# HandHeld_Terminal_V2.net
KiCad netlist of a schematic drawn in Altium Designer
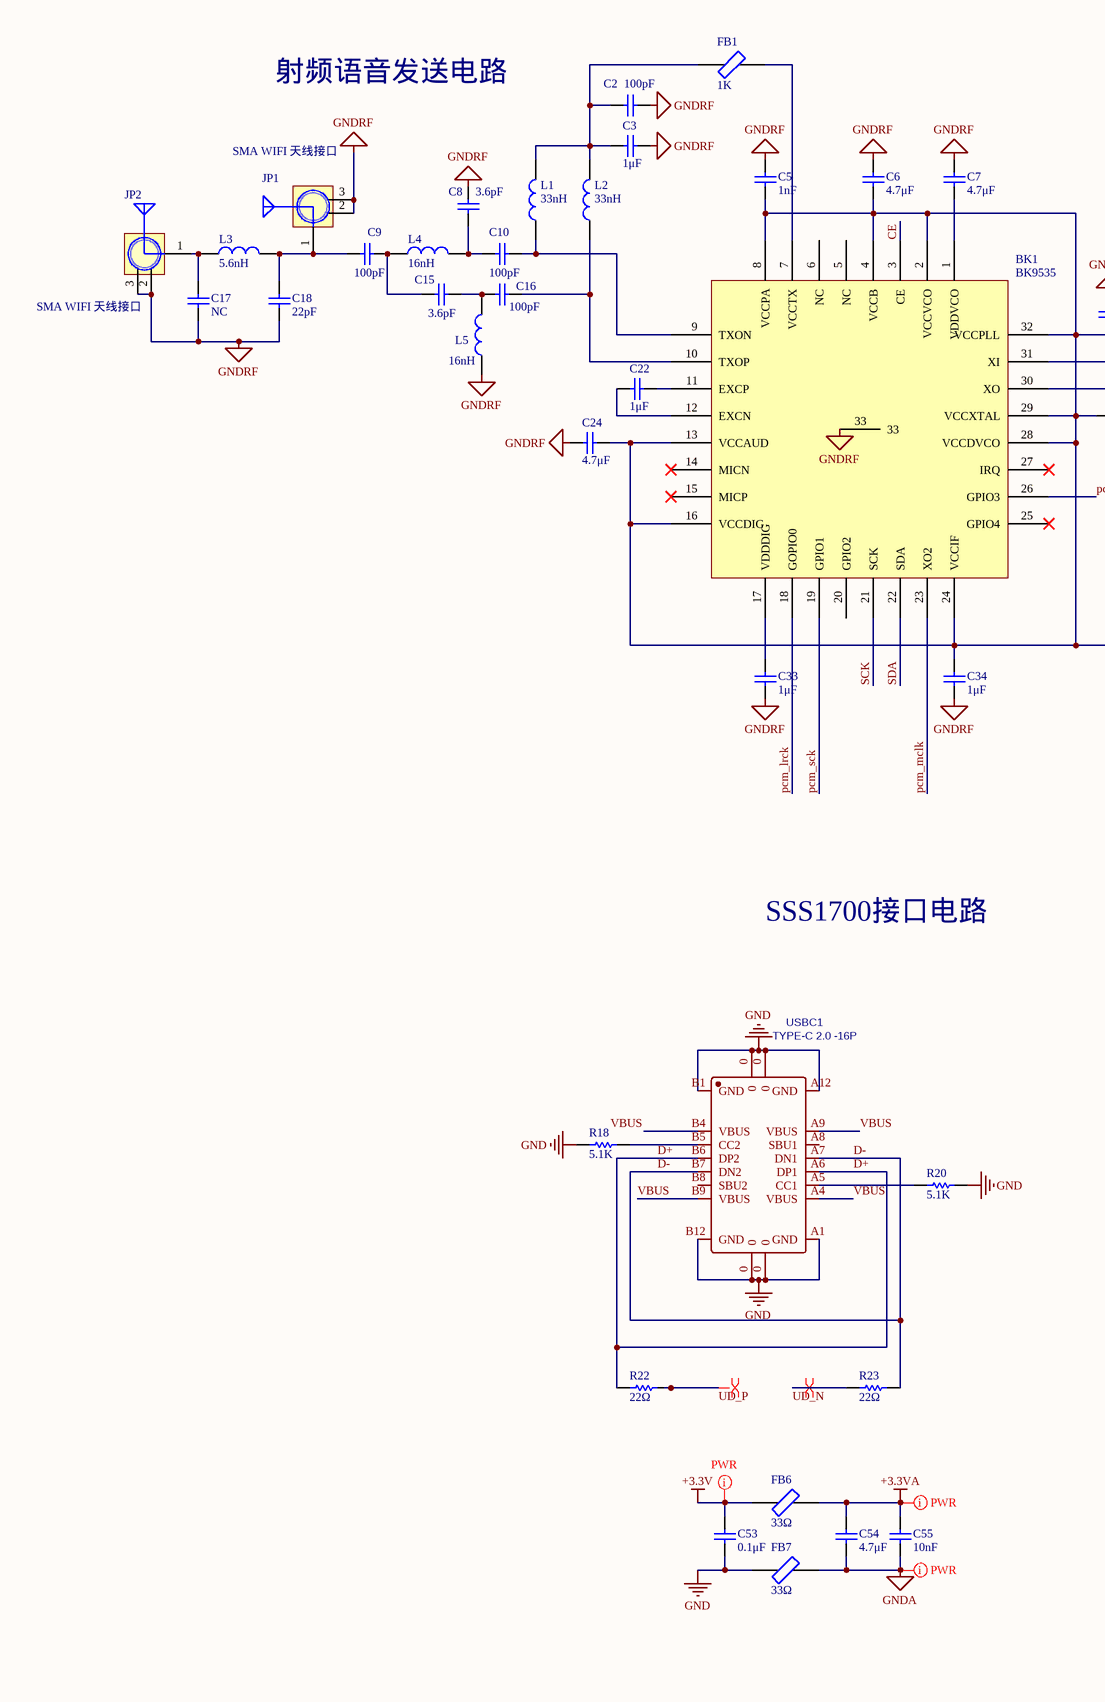
[diagram p0: HandHeld_Terminal_V2.SchDoc, left]
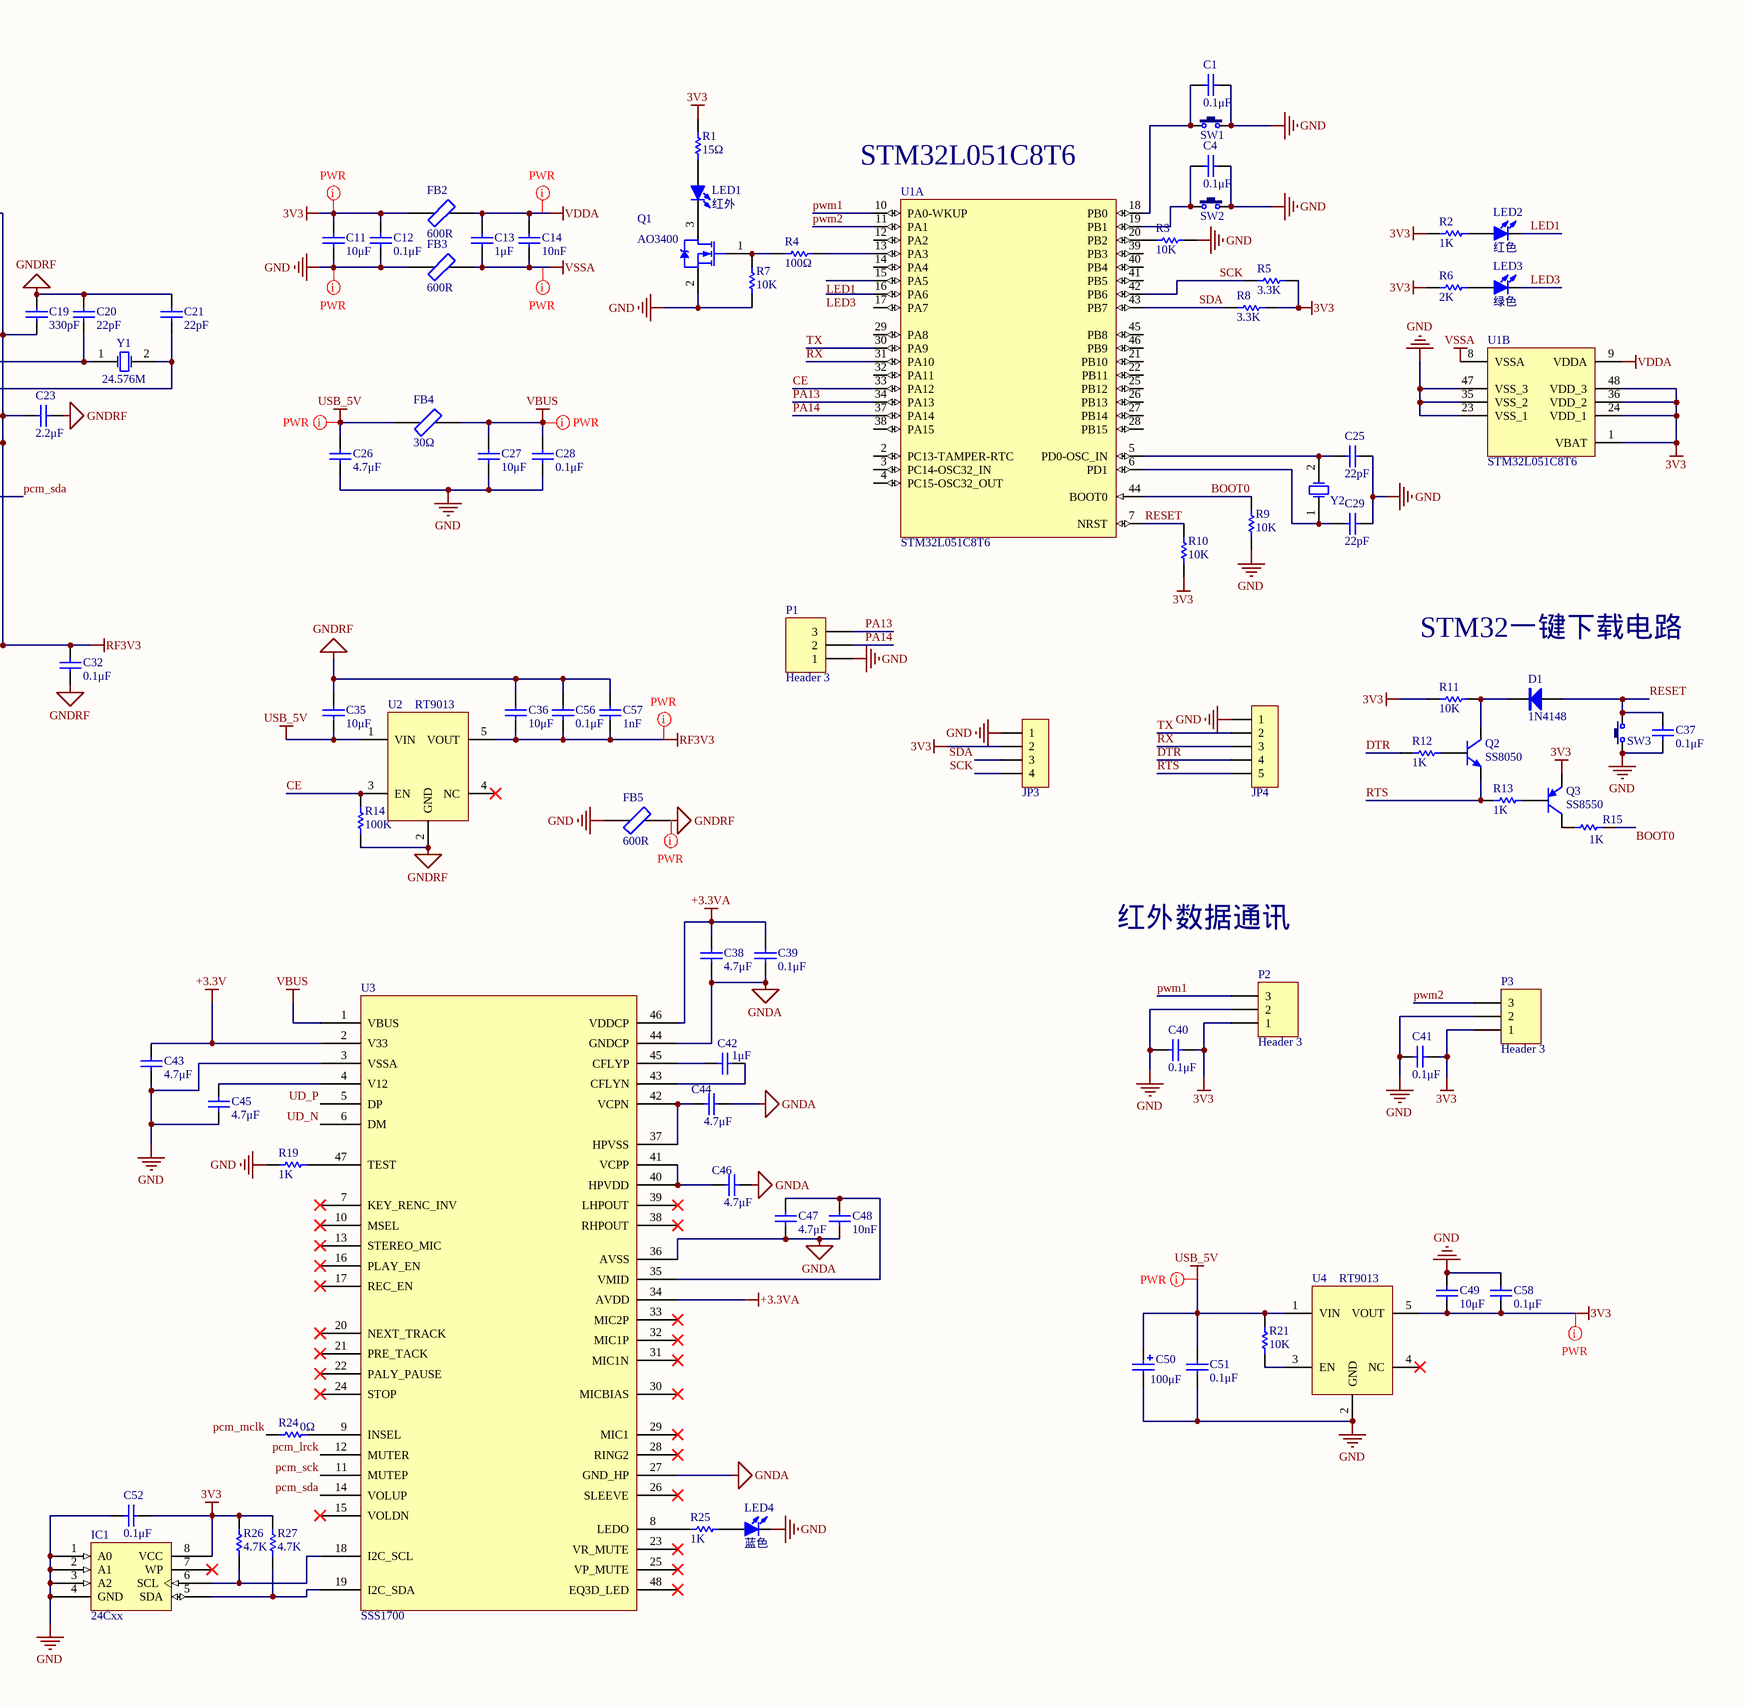
[diagram p1: HandHeld_Terminal_V2.SchDoc, right]

(export (version "E")
  (design (tool "Eeschema 10.0.6"))
  (components
    (comp (ref "BK1") (value "BK9535") (footprint "QFN32 5x5_N") (libsource (lib "Nixie") (part "BK9530")))
    (comp (ref "C1")
      (value "0.1μF")
      (footprint "C 0603_L")
      (description "Capacitor")
      (fields (field (name "Comment") "Cap") (field (name "PUBLISHER") "Altium Limited"))
      (libsource (lib "Nixie") (part "Cap"))
    )
    (comp (ref "C2")
      (value "100pF")
      (footprint "C 0603_L")
      (description "Capacitor")
      (fields (field (name "Comment") "Cap") (field (name "PUBLISHER") "Altium Limited"))
      (libsource (lib "Nixie") (part "Cap"))
    )
    (comp (ref "C3")
      (value "1μF")
      (footprint "C 0603_L")
      (description "Capacitor")
      (fields (field (name "Comment") "Cap") (field (name "PUBLISHER") "Altium Limited"))
      (libsource (lib "Nixie") (part "Cap"))
    )
    (comp (ref "C4")
      (value "0.1μF")
      (footprint "C 0603_L")
      (description "Capacitor")
      (fields (field (name "Comment") "Cap") (field (name "PUBLISHER") "Altium Limited"))
      (libsource (lib "Nixie") (part "Cap"))
    )
    (comp (ref "C5")
      (value "1nF")
      (footprint "C 0603_L")
      (description "Capacitor")
      (fields (field (name "Comment") "Cap") (field (name "PUBLISHER") "Altium Limited"))
      (libsource (lib "Nixie") (part "Cap"))
    )
    (comp (ref "C6")
      (value "4.7μF")
      (footprint "C 0603_L")
      (description "Capacitor")
      (fields (field (name "Comment") "Cap") (field (name "PUBLISHER") "Altium Limited"))
      (libsource (lib "Nixie") (part "Cap"))
    )
    (comp (ref "C7")
      (value "4.7μF")
      (footprint "C 0603_L")
      (description "Capacitor")
      (fields (field (name "Comment") "Cap") (field (name "PUBLISHER") "Altium Limited"))
      (libsource (lib "Nixie") (part "Cap"))
    )
    (comp (ref "C8")
      (value "3.6pF")
      (footprint "C 0603_L")
      (description "Capacitor")
      (fields (field (name "Comment") "Cap") (field (name "PUBLISHER") "Altium Limited"))
      (libsource (lib "Nixie") (part "Cap"))
    )
    (comp (ref "C9")
      (value "100pF")
      (footprint "C 0603_L")
      (description "Capacitor")
      (fields (field (name "Comment") "Cap") (field (name "PUBLISHER") "Altium Limited"))
      (libsource (lib "Nixie") (part "Cap"))
    )
    (comp (ref "C10")
      (value "100pF")
      (footprint "C 0603_L")
      (description "Capacitor")
      (fields (field (name "Comment") "Cap") (field (name "PUBLISHER") "Altium Limited"))
      (libsource (lib "Nixie") (part "Cap"))
    )
    (comp (ref "C11")
      (value "10μF")
      (footprint "C 0805_L")
      (description "Capacitor")
      (fields (field (name "Comment") "Cap") (field (name "PUBLISHER") "Altium Limited"))
      (libsource (lib "Nixie") (part "Cap"))
    )
    (comp (ref "C12")
      (value "0.1μF")
      (footprint "C 0603_L")
      (description "Capacitor")
      (fields (field (name "Comment") "Cap") (field (name "PUBLISHER") "Altium Limited"))
      (libsource (lib "Nixie") (part "Cap"))
    )
    (comp (ref "C13")
      (value "1μF")
      (footprint "C 0805_L")
      (description "Capacitor")
      (fields (field (name "Comment") "Cap") (field (name "PUBLISHER") "Altium Limited"))
      (libsource (lib "Nixie") (part "Cap"))
    )
    (comp (ref "C14")
      (value "10nF")
      (footprint "C 0805_L")
      (description "Capacitor")
      (fields (field (name "Comment") "Cap") (field (name "PUBLISHER") "Altium Limited"))
      (libsource (lib "Nixie") (part "Cap"))
    )
    (comp (ref "C15")
      (value "3.6pF")
      (footprint "C 0603_L")
      (description "Capacitor")
      (fields (field (name "Comment") "Cap") (field (name "PUBLISHER") "Altium Limited"))
      (libsource (lib "Nixie") (part "Cap"))
    )
    (comp (ref "C16")
      (value "100pF")
      (footprint "C 0603_L")
      (description "Capacitor")
      (fields (field (name "Comment") "Cap") (field (name "PUBLISHER") "Altium Limited"))
      (libsource (lib "Nixie") (part "Cap"))
    )
    (comp (ref "C17")
      (value "NC")
      (footprint "C 0603_L")
      (description "Capacitor")
      (fields (field (name "Comment") "Cap") (field (name "PUBLISHER") "Altium Limited"))
      (libsource (lib "Nixie") (part "Cap"))
    )
    (comp (ref "C18")
      (value "22pF")
      (footprint "C 0603_L")
      (description "Capacitor")
      (fields (field (name "Comment") "Cap") (field (name "PUBLISHER") "Altium Limited"))
      (libsource (lib "Nixie") (part "Cap"))
    )
    (comp (ref "C19")
      (value "330pF")
      (footprint "C 0603_L")
      (description "Capacitor")
      (fields (field (name "Comment") "Cap") (field (name "PUBLISHER") "Altium Limited"))
      (libsource (lib "Nixie") (part "Cap"))
    )
    (comp (ref "C20")
      (value "22pF")
      (footprint "C 0603_L")
      (description "Capacitor")
      (fields (field (name "Comment") "Cap") (field (name "PUBLISHER") "Altium Limited"))
      (libsource (lib "Nixie") (part "Cap"))
    )
    (comp (ref "C21")
      (value "22pF")
      (footprint "C 0603_L")
      (description "Capacitor")
      (fields (field (name "Comment") "Cap") (field (name "PUBLISHER") "Altium Limited"))
      (libsource (lib "Nixie") (part "Cap"))
    )
    (comp (ref "C22")
      (value "1μF")
      (footprint "C 0603_L")
      (description "Capacitor")
      (fields (field (name "Comment") "Cap") (field (name "PUBLISHER") "Altium Limited"))
      (libsource (lib "Nixie") (part "Cap"))
    )
    (comp (ref "C23")
      (value "2.2μF")
      (footprint "C 0603_L")
      (description "Capacitor")
      (fields (field (name "Comment") "Cap") (field (name "PUBLISHER") "Altium Limited"))
      (libsource (lib "Nixie") (part "Cap"))
    )
    (comp (ref "C24")
      (value "4.7μF")
      (footprint "C 0603_L")
      (description "Capacitor")
      (fields (field (name "Comment") "Cap") (field (name "PUBLISHER") "Altium Limited"))
      (libsource (lib "Nixie") (part "Cap"))
    )
    (comp (ref "C25")
      (value "22pF")
      (footprint "C 0603_L")
      (description "Capacitor")
      (fields (field (name "Comment") "Cap") (field (name "PUBLISHER") "Altium Limited"))
      (libsource (lib "Nixie") (part "Cap"))
    )
    (comp (ref "C26")
      (value "4.7μF")
      (footprint "C 0805_L")
      (description "Capacitor")
      (fields (field (name "Comment") "Cap") (field (name "PUBLISHER") "Altium Limited"))
      (libsource (lib "Nixie") (part "Cap"))
    )
    (comp (ref "C27")
      (value "10μF")
      (footprint "C 0805_L")
      (description "Capacitor")
      (fields (field (name "Comment") "Cap") (field (name "PUBLISHER") "Altium Limited"))
      (libsource (lib "Nixie") (part "Cap"))
    )
    (comp (ref "C28")
      (value "0.1μF")
      (footprint "C 0603_L")
      (description "Capacitor")
      (fields (field (name "Comment") "Cap") (field (name "PUBLISHER") "Altium Limited"))
      (libsource (lib "Nixie") (part "Cap"))
    )
    (comp (ref "C29")
      (value "22pF")
      (footprint "C 0603_L")
      (description "Capacitor")
      (fields (field (name "Comment") "Cap") (field (name "PUBLISHER") "Altium Limited"))
      (libsource (lib "Nixie") (part "Cap"))
    )
    (comp (ref "C32")
      (value "0.1μF")
      (footprint "C 0603_L")
      (description "Capacitor")
      (fields (field (name "Comment") "Cap") (field (name "PUBLISHER") "Altium Limited"))
      (libsource (lib "Nixie") (part "Cap"))
    )
    (comp (ref "C33")
      (value "1μF")
      (footprint "C 0603_L")
      (description "Capacitor")
      (fields (field (name "Comment") "Cap") (field (name "PUBLISHER") "Altium Limited"))
      (libsource (lib "Nixie") (part "Cap"))
    )
    (comp (ref "C34")
      (value "1μF")
      (footprint "C 0603_L")
      (description "Capacitor")
      (fields (field (name "Comment") "Cap") (field (name "PUBLISHER") "Altium Limited"))
      (libsource (lib "Nixie") (part "Cap"))
    )
    (comp (ref "C35")
      (value "10μF")
      (footprint "C 0805_L")
      (description "Capacitor")
      (fields (field (name "Comment") "Cap") (field (name "PUBLISHER") "Altium Limited"))
      (libsource (lib "Nixie") (part "Cap"))
    )
    (comp (ref "C36")
      (value "10μF")
      (footprint "C 0805_L")
      (description "Capacitor")
      (fields (field (name "Comment") "Cap") (field (name "PUBLISHER") "Altium Limited"))
      (libsource (lib "Nixie") (part "Cap"))
    )
    (comp (ref "C37")
      (value "0.1μF")
      (footprint "C 0603_L")
      (description "Capacitor")
      (fields (field (name "Comment") "Cap") (field (name "PUBLISHER") "Altium Limited"))
      (libsource (lib "Nixie") (part "Cap"))
    )
    (comp (ref "C38")
      (value "4.7μF")
      (footprint "C 0603_L")
      (description "Capacitor")
      (fields (field (name "Comment") "Cap") (field (name "PUBLISHER") "Altium Limited"))
      (libsource (lib "Nixie") (part "Cap"))
    )
    (comp (ref "C39")
      (value "0.1μF")
      (footprint "C 0603_L")
      (description "Capacitor")
      (fields (field (name "Comment") "Cap") (field (name "PUBLISHER") "Altium Limited"))
      (libsource (lib "Nixie") (part "Cap"))
    )
    (comp (ref "C40")
      (value "0.1μF")
      (footprint "C 0603_L")
      (description "Capacitor")
      (fields (field (name "Comment") "Cap") (field (name "PUBLISHER") "Altium Limited"))
      (libsource (lib "Nixie") (part "Cap"))
    )
    (comp (ref "C41")
      (value "0.1μF")
      (footprint "C 0603_L")
      (description "Capacitor")
      (fields (field (name "Comment") "Cap") (field (name "PUBLISHER") "Altium Limited"))
      (libsource (lib "Nixie") (part "Cap"))
    )
    (comp (ref "C42")
      (value "1μF")
      (footprint "C 0603_L")
      (description "Capacitor")
      (fields (field (name "Comment") "Cap") (field (name "PUBLISHER") "Altium Limited"))
      (libsource (lib "Nixie") (part "Cap"))
    )
    (comp (ref "C43")
      (value "4.7μF")
      (footprint "C 0603_L")
      (description "Capacitor")
      (fields (field (name "Comment") "Cap") (field (name "PUBLISHER") "Altium Limited"))
      (libsource (lib "Nixie") (part "Cap"))
    )
    (comp (ref "C44")
      (value "4.7μF")
      (footprint "C 0603_L")
      (description "Capacitor")
      (fields (field (name "Comment") "Cap") (field (name "PUBLISHER") "Altium Limited"))
      (libsource (lib "Nixie") (part "Cap"))
    )
    (comp (ref "C45")
      (value "4.7μF")
      (footprint "C 0603_L")
      (description "Capacitor")
      (fields (field (name "Comment") "Cap") (field (name "PUBLISHER") "Altium Limited"))
      (libsource (lib "Nixie") (part "Cap"))
    )
    (comp (ref "C46")
      (value "4.7μF")
      (footprint "C 0603_L")
      (description "Capacitor")
      (fields (field (name "Comment") "Cap") (field (name "PUBLISHER") "Altium Limited"))
      (libsource (lib "Nixie") (part "Cap"))
    )
    (comp (ref "C47")
      (value "4.7μF")
      (footprint "C 0603_L")
      (description "Capacitor")
      (fields (field (name "Comment") "Cap") (field (name "PUBLISHER") "Altium Limited"))
      (libsource (lib "Nixie") (part "Cap"))
    )
    (comp (ref "C48")
      (value "10nF")
      (footprint "C 0603_L")
      (description "Capacitor")
      (fields (field (name "Comment") "Cap") (field (name "PUBLISHER") "Altium Limited"))
      (libsource (lib "Nixie") (part "Cap"))
    )
    (comp (ref "C49")
      (value "10μF")
      (footprint "C 0805_L")
      (description "Capacitor")
      (fields (field (name "Comment") "Cap") (field (name "PUBLISHER") "Altium Limited"))
      (libsource (lib "Nixie") (part "Cap"))
    )
    (comp (ref "C50")
      (value "100μF")
      (footprint "CM C(5*5.4)")
      (description "Polarized Capacitor (Radial)")
      (fields (field (name "Comment") "Cap Pol1") (field (name "PUBLISHER") "Altium Limited"))
      (libsource (lib "Nixie") (part "Cap Pol1"))
    )
    (comp (ref "C51")
      (value "0.1μF")
      (footprint "C 0603_L")
      (description "Capacitor")
      (fields (field (name "Comment") "Cap") (field (name "PUBLISHER") "Altium Limited"))
      (libsource (lib "Nixie") (part "Cap"))
    )
    (comp (ref "C52")
      (value "0.1μF")
      (footprint "C 0603_L")
      (description "Capacitor")
      (fields (field (name "Comment") "Cap") (field (name "PUBLISHER") "Altium Limited"))
      (libsource (lib "Nixie") (part "Cap"))
    )
    (comp (ref "C53")
      (value "0.1μF")
      (footprint "C 0603_L")
      (description "Capacitor")
      (fields (field (name "Comment") "Cap") (field (name "PUBLISHER") "Altium Limited"))
      (libsource (lib "Nixie") (part "Cap"))
    )
    (comp (ref "C54")
      (value "4.7μF")
      (footprint "C 0805_L")
      (description "Capacitor")
      (fields (field (name "Comment") "Cap") (field (name "PUBLISHER") "Altium Limited"))
      (libsource (lib "Nixie") (part "Cap"))
    )
    (comp (ref "C55")
      (value "10nF")
      (footprint "C 0603_L")
      (description "Capacitor")
      (fields (field (name "Comment") "Cap") (field (name "PUBLISHER") "Altium Limited"))
      (libsource (lib "Nixie") (part "Cap"))
    )
    (comp (ref "C56")
      (value "0.1μF")
      (footprint "C 0603_L")
      (description "Capacitor")
      (fields (field (name "Comment") "Cap") (field (name "PUBLISHER") "Altium Limited"))
      (libsource (lib "Nixie") (part "Cap"))
    )
    (comp (ref "C57")
      (value "1nF")
      (footprint "C 0603_L")
      (description "Capacitor")
      (fields (field (name "Comment") "Cap") (field (name "PUBLISHER") "Altium Limited"))
      (libsource (lib "Nixie") (part "Cap"))
    )
    (comp (ref "C58")
      (value "0.1μF")
      (footprint "C 0603_L")
      (description "Capacitor")
      (fields (field (name "Comment") "Cap") (field (name "PUBLISHER") "Altium Limited"))
      (libsource (lib "Nixie") (part "Cap"))
    )
    (comp (ref "D1")
      (value "1N4148")
      (footprint "SOD-323")
      (description "开关二极管")
      (libsource (lib "Nixie") (part "1N4148"))
    )
    (comp (ref "FB1")
      (value "1K")
      (footprint "C 0603_L")
      (description "铁氧体磁珠")
      (fields (field (name "Comment") "Ferrite bead"))
      (libsource (lib "Nixie") (part "Ferrite bead"))
    )
    (comp (ref "FB2")
      (value "600R")
      (footprint "C 0603_L")
      (description "铁氧体磁珠")
      (fields (field (name "Comment") "Ferrite bead"))
      (libsource (lib "Nixie") (part "Ferrite bead"))
    )
    (comp (ref "FB3")
      (value "600R")
      (footprint "C 0603_L")
      (description "铁氧体磁珠")
      (fields (field (name "Comment") "Ferrite bead"))
      (libsource (lib "Nixie") (part "Ferrite bead"))
    )
    (comp (ref "FB4")
      (value "30Ω")
      (footprint "C 0603_L")
      (description "铁氧体磁珠")
      (fields (field (name "Comment") "Ferrite bead"))
      (libsource (lib "Nixie") (part "Ferrite bead"))
    )
    (comp (ref "FB5")
      (value "600R")
      (footprint "C 0805_L")
      (description "铁氧体磁珠")
      (fields (field (name "Comment") "Ferrite bead"))
      (libsource (lib "Nixie") (part "Ferrite bead"))
    )
    (comp (ref "FB6")
      (value "33Ω")
      (footprint "C 0603_L")
      (description "铁氧体磁珠")
      (fields (field (name "Comment") "Ferrite bead"))
      (libsource (lib "Nixie") (part "Ferrite bead"))
    )
    (comp (ref "FB7")
      (value "33Ω")
      (footprint "C 0603_L")
      (description "铁氧体磁珠")
      (fields (field (name "Comment") "Ferrite bead"))
      (libsource (lib "Nixie") (part "Ferrite bead"))
    )
    (comp (ref "IC1")
      (value "24Cxx")
      (footprint "SOP8_L")
      (description "外置EEPROM")
      (fields (field (name "版权归属") "封装库来自淘宝 ID：黄晶宝石"))
      (libsource (lib "Nixie") (part "24Cxx"))
    )
    (comp (ref "JP1")
      (value "SMA WIFI 天线接口")
      (footprint "COAXIAL/SMD/CON/V/I-PEX/W08-5801")
      (description "SMA-2.4G射频天线接口")
      (fields (field (name "版权归属") "封装库来自淘宝 ID：黄晶宝石"))
      (libsource (lib "") (part "SMA_1"))
    )
    (comp (ref "JP2")
      (value "SMA WIFI 天线接口")
      (footprint "SMA-KE")
      (description "SMA-2.4G射频天线接口")
      (fields (field (name "版权归属") "封装库来自淘宝 ID：黄晶宝石"))
      (libsource (lib "Nixie") (part "SMA"))
    )
    (comp (ref "JP3")
      (value "HDR-1X4")
      (footprint "HDR2.54-LI-4P")
      (description "4P接插件")
      (fields (field (name "版权归属") "封装库来自淘宝 ID：黄晶宝石"))
      (libsource (lib "Nixie") (part "Header 4"))
    )
    (comp (ref "JP4")
      (value "HDR-1X5")
      (footprint "HDR2.0-LI-5P")
      (description "5P接插件")
      (fields (field (name "版权归属") "封装库来自淘宝 ID：黄晶宝石"))
      (libsource (lib "Nixie") (part "Header 5"))
    )
    (comp (ref "L1")
      (value "33nH")
      (footprint "L 0603")
      (description "小功率贴片电感")
      (fields (field (name "Comment") "L"))
      (libsource (lib "Nixie") (part "L"))
    )
    (comp (ref "L2")
      (value "33nH")
      (footprint "L 0603")
      (description "小功率贴片电感")
      (fields (field (name "Comment") "L"))
      (libsource (lib "Nixie") (part "L"))
    )
    (comp (ref "L3")
      (value "5.6nH")
      (footprint "L 0603")
      (description "小功率贴片电感")
      (fields (field (name "Comment") "L"))
      (libsource (lib "Nixie") (part "L"))
    )
    (comp (ref "L4")
      (value "16nH")
      (footprint "L 0603")
      (description "小功率贴片电感")
      (fields (field (name "Comment") "L"))
      (libsource (lib "Nixie") (part "L"))
    )
    (comp (ref "L5")
      (value "16nH")
      (footprint "L 0603")
      (description "小功率贴片电感")
      (fields (field (name "Comment") "L"))
      (libsource (lib "Nixie") (part "L"))
    )
    (comp (ref "LED1")
      (value "红外")
      (footprint "LED 3MM-R")
      (description "贴片LED")
      (fields (field (name "版权归属") "封装库来自淘宝 ID：黄晶宝石"))
      (libsource (lib "Nixie") (part "LED-SMD"))
    )
    (comp (ref "LED2")
      (value "红色")
      (footprint "LED 0805R")
      (description "贴片LED")
      (fields (field (name "版权归属") "封装库来自淘宝 ID：黄晶宝石"))
      (libsource (lib "Nixie") (part "LED-SMD"))
    )
    (comp (ref "LED3")
      (value "绿色")
      (footprint "LED 0805G")
      (description "贴片LED")
      (fields (field (name "版权归属") "封装库来自淘宝 ID：黄晶宝石"))
      (libsource (lib "Nixie") (part "LED-SMD"))
    )
    (comp (ref "LED4")
      (value "蓝色")
      (footprint "LED 0805B")
      (description "贴片LED")
      (fields (field (name "版权归属") "封装库来自淘宝 ID：黄晶宝石"))
      (libsource (lib "Nixie") (part "LED-SMD"))
    )
    (comp (ref "P1")
      (value "Header 3")
      (footprint "HDR2.54-LI-3P")
      (description "Header, 3-Pin")
      (fields (field (name "PUBLISHER") "Altium Limited"))
      (libsource (lib "") (part "Header 3_1"))
    )
    (comp (ref "P2")
      (value "Header 3")
      (footprint "HDR1X3")
      (description "Header, 3-Pin")
      (fields (field (name "PUBLISHER") "Altium Limited"))
      (libsource (lib "Miscellaneous Connectors") (part "Header 3"))
    )
    (comp (ref "P3")
      (value "Header 3")
      (footprint "HDR1X3")
      (description "Header, 3-Pin")
      (fields (field (name "PUBLISHER") "Altium Limited"))
      (libsource (lib "Miscellaneous Connectors") (part "Header 3"))
    )
    (comp (ref "Q1")
      (value "AO3400")
      (footprint "SOT-23-3L")
      (description "N-Channel Power MOSFET")
      (fields (field (name "PUBLISHER") "Altium Limited"))
      (libsource (lib "Nixie") (part "NMOS-2"))
    )
    (comp (ref "Q2")
      (value "SS8050")
      (footprint "SOT-23-3L")
      (description "高频放大-NPN型")
      (fields (field (name "版权归属") "封装库来自淘宝 ID：黄晶宝石"))
      (libsource (lib "Nixie") (part "8050-SMD"))
    )
    (comp (ref "Q3")
      (value "SS8550")
      (footprint "SOT-23-3L")
      (description "高频放大-PNP型")
      (fields (field (name "版权归属") "封装库来自淘宝 ID：黄晶宝石"))
      (libsource (lib "Nixie") (part "8550-SMD"))
    )
    (comp (ref "R1")
      (value "15Ω")
      (footprint "R 1206_L")
      (description "Resistor")
      (fields (field (name "PUBLISHER") "Altium Limited"))
      (libsource (lib "Nixie") (part "Resistor"))
    )
    (comp (ref "R2")
      (value "1K")
      (footprint "R 0603_L")
      (description "Resistor")
      (fields (field (name "PUBLISHER") "Altium Limited"))
      (libsource (lib "Nixie") (part "Resistor"))
    )
    (comp (ref "R3")
      (value "10K")
      (footprint "R 0603_L")
      (description "Resistor")
      (fields (field (name "PUBLISHER") "Altium Limited"))
      (libsource (lib "Nixie") (part "Resistor"))
    )
    (comp (ref "R4")
      (value "100Ω")
      (footprint "R 0603_L")
      (description "Resistor")
      (fields (field (name "PUBLISHER") "Altium Limited"))
      (libsource (lib "Nixie") (part "Resistor"))
    )
    (comp (ref "R5")
      (value "3.3K")
      (footprint "R 0603_L")
      (description "Resistor")
      (fields (field (name "PUBLISHER") "Altium Limited"))
      (libsource (lib "Nixie") (part "Resistor"))
    )
    (comp (ref "R6")
      (value "2K")
      (footprint "R 0603_L")
      (description "Resistor")
      (fields (field (name "PUBLISHER") "Altium Limited"))
      (libsource (lib "Nixie") (part "Resistor"))
    )
    (comp (ref "R7")
      (value "10K")
      (footprint "R 0603_L")
      (description "Resistor")
      (fields (field (name "PUBLISHER") "Altium Limited"))
      (libsource (lib "Nixie") (part "Resistor"))
    )
    (comp (ref "R8")
      (value "3.3K")
      (footprint "R 0603_L")
      (description "Resistor")
      (fields (field (name "PUBLISHER") "Altium Limited"))
      (libsource (lib "Nixie") (part "Resistor"))
    )
    (comp (ref "R9")
      (value "10K")
      (footprint "R 0603_L")
      (description "Resistor")
      (fields (field (name "PUBLISHER") "Altium Limited"))
      (libsource (lib "Nixie") (part "Resistor"))
    )
    (comp (ref "R10")
      (value "10K")
      (footprint "R 0603_L")
      (description "Resistor")
      (fields (field (name "PUBLISHER") "Altium Limited"))
      (libsource (lib "Nixie") (part "Resistor"))
    )
    (comp (ref "R11")
      (value "10K")
      (footprint "R 0603_L")
      (description "Resistor")
      (fields (field (name "PUBLISHER") "Altium Limited"))
      (libsource (lib "Nixie") (part "Resistor"))
    )
    (comp (ref "R12")
      (value "1K")
      (footprint "R 0603_L")
      (description "Resistor")
      (fields (field (name "PUBLISHER") "Altium Limited"))
      (libsource (lib "Nixie") (part "Resistor"))
    )
    (comp (ref "R13")
      (value "1K")
      (footprint "R 0603_L")
      (description "Resistor")
      (fields (field (name "PUBLISHER") "Altium Limited"))
      (libsource (lib "Nixie") (part "Resistor"))
    )
    (comp (ref "R14")
      (value "100K")
      (footprint "R 0603_L")
      (description "Resistor")
      (fields (field (name "PUBLISHER") "Altium Limited"))
      (libsource (lib "Nixie") (part "Resistor"))
    )
    (comp (ref "R15")
      (value "1K")
      (footprint "R 0603_L")
      (description "Resistor")
      (fields (field (name "PUBLISHER") "Altium Limited"))
      (libsource (lib "Nixie") (part "Resistor"))
    )
    (comp (ref "R18")
      (value "5.1K")
      (footprint "R 0603_L")
      (description "Resistor")
      (fields (field (name "PUBLISHER") "Altium Limited"))
      (libsource (lib "Nixie") (part "Resistor"))
    )
    (comp (ref "R19")
      (value "1K")
      (footprint "R 0603_L")
      (description "Resistor")
      (fields (field (name "PUBLISHER") "Altium Limited"))
      (libsource (lib "Nixie") (part "Resistor"))
    )
    (comp (ref "R20")
      (value "5.1K")
      (footprint "R 0603_L")
      (description "Resistor")
      (fields (field (name "PUBLISHER") "Altium Limited"))
      (libsource (lib "Nixie") (part "Resistor"))
    )
    (comp (ref "R21")
      (value "10K")
      (footprint "R 0603_L")
      (description "Resistor")
      (fields (field (name "PUBLISHER") "Altium Limited"))
      (libsource (lib "Nixie") (part "Resistor"))
    )
    (comp (ref "R22")
      (value "22Ω")
      (footprint "R 0603_L")
      (description "Resistor")
      (fields (field (name "PUBLISHER") "Altium Limited"))
      (libsource (lib "Nixie") (part "Resistor"))
    )
    (comp (ref "R23")
      (value "22Ω")
      (footprint "R 0603_L")
      (description "Resistor")
      (fields (field (name "PUBLISHER") "Altium Limited"))
      (libsource (lib "Nixie") (part "Resistor"))
    )
    (comp (ref "R24")
      (value "0Ω")
      (footprint "R 0603_L")
      (description "Resistor")
      (fields (field (name "PUBLISHER") "Altium Limited"))
      (libsource (lib "Nixie") (part "Resistor"))
    )
    (comp (ref "R25")
      (value "1K")
      (footprint "R 0603_L")
      (description "Resistor")
      (fields (field (name "PUBLISHER") "Altium Limited"))
      (libsource (lib "Nixie") (part "Resistor"))
    )
    (comp (ref "R26")
      (value "4.7K")
      (footprint "R 0603_L")
      (description "Resistor")
      (fields (field (name "PUBLISHER") "Altium Limited"))
      (libsource (lib "Nixie") (part "Resistor"))
    )
    (comp (ref "R27")
      (value "4.7K")
      (footprint "R 0603_L")
      (description "Resistor")
      (fields (field (name "PUBLISHER") "Altium Limited"))
      (libsource (lib "Nixie") (part "Resistor"))
    )
    (comp (ref "SW1")
      (value "3x6x5")
      (footprint "TSW SMD-3*6*2.5")
      (description "3x6轻触开关")
      (fields (field (name "版权归属") "封装库来自淘宝 ID：黄晶宝石"))
      (libsource (lib "") (part "TSW 3x6_1"))
    )
    (comp (ref "SW2")
      (value "3x6x5")
      (footprint "TSW SMD-3*6*2.5")
      (description "3x6轻触开关")
      (fields (field (name "版权归属") "封装库来自淘宝 ID：黄晶宝石"))
      (libsource (lib "") (part "TSW 3x6_1"))
    )
    (comp (ref "SW3")
      (value "3x6x5")
      (footprint "TSW SMD-3*6*2.5")
      (description "3x6轻触开关")
      (fields (field (name "版权归属") "封装库来自淘宝 ID：黄晶宝石"))
      (libsource (lib "Nixie") (part "TSW 3x6"))
    )
    (comp (ref "U1")
      (value "STM32L051C8T6")
      (footprint "LQFP48_L")
      (description "ARM")
      (libsource (lib "Nixie") (part "STM32F103C8T6"))
    )
    (comp (ref "U2")
      (value "RT9013")
      (footprint "SOT23-5L")
      (description "LDO")
      (libsource (lib "HandHeld_terminal") (part "RT9013"))
    )
    (comp (ref "U3")
      (value "SSS1700")
      (footprint "LQFP48_L")
      (description "USB音频芯片")
      (libsource (lib "Nixie") (part "SSS1700"))
    )
    (comp (ref "U4")
      (value "RT9013")
      (footprint "SOT23-5L")
      (description "LDO")
      (libsource (lib "HandHeld_terminal") (part "RT9013"))
    )
    (comp (ref "USBC1")
      (value "TYPE-C 2.0 -16P")
      (footprint "USB-C-SMD_TYPE-C-USB-5")
      (description "USB2.0 Type-C 母座 16Pin")
      (libsource (lib "Nixie") (part "USB2.0 Type-C 16Pin母座"))
    )
    (comp (ref "Y1")
      (value "24.576M")
      (footprint "OSC 5032-2P")
      (description "Crystal Oscillator")
      (fields (field (name "PUBLISHER") "Altium Limited"))
      (libsource (lib "Miscellaneous Devices") (part "XTAL"))
    )
    (comp (ref "Y2")
      (value "8MHz ±20ppm 20pF")
      (footprint "OSC 5032-2P")
      (description "贴片晶振")
      (libsource (lib "HandHeld_terminal") (part "SMD-5032_2P 8MHz 20ppm 20pF"))
    )
  )
  (nets
    (net (code "1") (name "+3.3V") (class "Default")
      (node (ref "C43") (pin "2") (pinfunction "2_2") (pintype "passive"))
      (node (ref "C53") (pin "2") (pinfunction "2_2") (pintype "passive"))
      (node (ref "FB6") (pin "1") (pinfunction "1_1") (pintype "passive"))
      (node (ref "U3") (pin "2") (pinfunction "V33_2") (pintype "passive"))
    )
    (net (code "2") (name "+3.3VA") (class "Default")
      (node (ref "C38") (pin "2") (pinfunction "2_2") (pintype "passive"))
      (node (ref "C39") (pin "2") (pinfunction "2_2") (pintype "passive"))
      (node (ref "C54") (pin "2") (pinfunction "2_2") (pintype "passive"))
      (node (ref "C55") (pin "2") (pinfunction "2_2") (pintype "passive"))
      (node (ref "FB6") (pin "2") (pinfunction "2_2") (pintype "passive"))
      (node (ref "U3") (pin "34") (pinfunction "AVDD_34") (pintype "passive"))
      (node (ref "U3") (pin "46") (pinfunction "VDDCP_46") (pintype "passive"))
    )
    (net (code "3") (name "/BOOT0") (class "Default")
      (node (ref "R15") (pin "2") (pinfunction "2_2") (pintype "passive"))
      (node (ref "R9") (pin "1") (pinfunction "1_1") (pintype "passive"))
      (node (ref "U1") (pin "44") (pinfunction "BOOT0_44") (pintype "input"))
    )
    (net (code "4") (name "/CE") (class "Default")
      (node (ref "BK1") (pin "3") (pinfunction "CE_3") (pintype "passive"))
      (node (ref "R14") (pin "2") (pinfunction "2_2") (pintype "passive"))
      (node (ref "U1") (pin "33") (pinfunction "PA12_33") (pintype "bidirectional"))
      (node (ref "U2") (pin "3") (pinfunction "EN_3") (pintype "passive"))
    )
    (net (code "5") (name "/D+") (class "Default")
      (node (ref "R22") (pin "1") (pinfunction "1_1") (pintype "passive"))
      (node (ref "USBC1") (pin "A6") (pinfunction "DP1_A6") (pintype "passive"))
      (node (ref "USBC1") (pin "B6") (pinfunction "DP2_B6") (pintype "passive"))
    )
    (net (code "6") (name "/D-") (class "Default")
      (node (ref "R23") (pin "2") (pinfunction "2_2") (pintype "passive"))
      (node (ref "USBC1") (pin "A7") (pinfunction "DN1_A7") (pintype "passive"))
      (node (ref "USBC1") (pin "B7") (pinfunction "DN2_B7") (pintype "passive"))
    )
    (net (code "7") (name "/DTR") (class "Default")
      (node (ref "JP4") (pin "4") (pinfunction "4_4") (pintype "passive"))
      (node (ref "R12") (pin "1") (pinfunction "1_1") (pintype "passive"))
    )
    (net (code "8") (name "/LED1") (class "Default")
      (node (ref "LED2") (pin "2") (pinfunction "K_2") (pintype "passive"))
      (node (ref "U1") (pin "15") (pinfunction "PA5_15") (pintype "bidirectional"))
    )
    (net (code "9") (name "/LED3") (class "Default")
      (node (ref "LED3") (pin "2") (pinfunction "K_2") (pintype "passive"))
      (node (ref "U1") (pin "16") (pinfunction "PA6_16") (pintype "bidirectional"))
    )
    (net (code "10") (name "/PA13") (class "Default")
      (node (ref "P1") (pin "3") (pinfunction "3_3") (pintype "passive"))
      (node (ref "U1") (pin "34") (pinfunction "PA13_34") (pintype "bidirectional"))
    )
    (net (code "11") (name "/PA14") (class "Default")
      (node (ref "P1") (pin "2") (pinfunction "2_2") (pintype "passive"))
      (node (ref "U1") (pin "37") (pinfunction "PA14_37") (pintype "bidirectional"))
    )
    (net (code "12") (name "/RESET") (class "Default")
      (node (ref "C37") (pin "2") (pinfunction "2_2") (pintype "passive"))
      (node (ref "D1") (pin "1") (pinfunction "A_1") (pintype "passive"))
      (node (ref "R10") (pin "1") (pinfunction "1_1") (pintype "passive"))
      (node (ref "SW3") (pin "2") (pinfunction "2_2") (pintype "passive"))
      (node (ref "U1") (pin "7") (pinfunction "NRST_7") (pintype "bidirectional"))
    )
    (net (code "13") (name "/RTS") (class "Default")
      (node (ref "JP4") (pin "5") (pinfunction "5_5") (pintype "passive"))
      (node (ref "Q2") (pin "2") (pinfunction "E_2") (pintype "passive"))
      (node (ref "R13") (pin "1") (pinfunction "1_1") (pintype "passive"))
    )
    (net (code "14") (name "/RX") (class "Default")
      (node (ref "JP4") (pin "3") (pinfunction "3_3") (pintype "passive"))
      (node (ref "U1") (pin "31") (pinfunction "PA10_31") (pintype "bidirectional"))
    )
    (net (code "15") (name "/SCK") (class "Default")
      (node (ref "BK1") (pin "21") (pinfunction "SCK_21") (pintype "passive"))
      (node (ref "JP3") (pin "4") (pinfunction "4_4") (pintype "passive"))
      (node (ref "R5") (pin "2") (pinfunction "2_2") (pintype "passive"))
      (node (ref "U1") (pin "42") (pinfunction "PB6_42") (pintype "bidirectional"))
    )
    (net (code "16") (name "/SDA") (class "Default")
      (node (ref "BK1") (pin "22") (pinfunction "SDA_22") (pintype "passive"))
      (node (ref "JP3") (pin "3") (pinfunction "3_3") (pintype "passive"))
      (node (ref "R8") (pin "2") (pinfunction "2_2") (pintype "passive"))
      (node (ref "U1") (pin "43") (pinfunction "PB7_43") (pintype "bidirectional"))
    )
    (net (code "17") (name "/TX") (class "Default")
      (node (ref "JP4") (pin "2") (pinfunction "2_2") (pintype "passive"))
      (node (ref "U1") (pin "30") (pinfunction "PA9_30") (pintype "bidirectional"))
    )
    (net (code "18") (name "/UD_N") (class "Default")
      (node (ref "R23") (pin "1") (pinfunction "1_1") (pintype "passive"))
      (node (ref "U3") (pin "6") (pinfunction "DM_6") (pintype "passive"))
    )
    (net (code "19") (name "/UD_P") (class "Default")
      (node (ref "R22") (pin "2") (pinfunction "2_2") (pintype "passive"))
      (node (ref "U3") (pin "5") (pinfunction "DP_5") (pintype "passive"))
    )
    (net (code "20") (name "/pcm_lrck") (class "Default")
      (node (ref "BK1") (pin "18") (pinfunction "GOPIO0_18") (pintype "passive"))
      (node (ref "U3") (pin "12") (pinfunction "MUTER_12") (pintype "passive"))
    )
    (net (code "21") (name "/pcm_mclk") (class "Default")
      (node (ref "BK1") (pin "23") (pinfunction "XO2_23") (pintype "passive"))
      (node (ref "R24") (pin "2") (pinfunction "2_2") (pintype "passive"))
    )
    (net (code "22") (name "/pcm_sck") (class "Default")
      (node (ref "BK1") (pin "19") (pinfunction "GPIO1_19") (pintype "passive"))
      (node (ref "U3") (pin "11") (pinfunction "MUTEP_11") (pintype "passive"))
    )
    (net (code "23") (name "/pcm_sda") (class "Default")
      (node (ref "BK1") (pin "26") (pinfunction "GPIO3_26") (pintype "passive"))
      (node (ref "U3") (pin "14") (pinfunction "VOLUP_14") (pintype "passive"))
    )
    (net (code "24") (name "/pwm1") (class "Default")
      (node (ref "P2") (pin "3") (pinfunction "3_3") (pintype "passive"))
      (node (ref "U1") (pin "10") (pinfunction "PA0-WKUP_10") (pintype "bidirectional"))
    )
    (net (code "25") (name "/pwm2") (class "Default")
      (node (ref "P3") (pin "3") (pinfunction "3_3") (pintype "passive"))
      (node (ref "U1") (pin "11") (pinfunction "PA1_11") (pintype "bidirectional"))
    )
    (net (code "26") (name "3V3") (class "Default")
      (node (ref "C11") (pin "2") (pinfunction "2_2") (pintype "passive"))
      (node (ref "C12") (pin "2") (pinfunction "2_2") (pintype "passive"))
      (node (ref "C40") (pin "1") (pinfunction "1_1") (pintype "passive"))
      (node (ref "C41") (pin "1") (pinfunction "1_1") (pintype "passive"))
      (node (ref "C49") (pin "1") (pinfunction "1_1") (pintype "passive"))
      (node (ref "C52") (pin "1") (pinfunction "1_1") (pintype "passive"))
      (node (ref "C58") (pin "2") (pinfunction "2_2") (pintype "passive"))
      (node (ref "FB2") (pin "1") (pinfunction "1_1") (pintype "passive"))
      (node (ref "IC1") (pin "8") (pinfunction "VCC_8") (pintype "power_in"))
      (node (ref "JP3") (pin "2") (pinfunction "2_2") (pintype "passive"))
      (node (ref "P2") (pin "1") (pinfunction "1_1") (pintype "passive"))
      (node (ref "P3") (pin "1") (pinfunction "1_1") (pintype "passive"))
      (node (ref "Q3") (pin "2") (pinfunction "E_2") (pintype "passive"))
      (node (ref "R1") (pin "2") (pinfunction "2_2") (pintype "passive"))
      (node (ref "R10") (pin "2") (pinfunction "2_2") (pintype "passive"))
      (node (ref "R11") (pin "1") (pinfunction "1_1") (pintype "passive"))
      (node (ref "R2") (pin "2") (pinfunction "2_2") (pintype "passive"))
      (node (ref "R26") (pin "2") (pinfunction "2_2") (pintype "passive"))
      (node (ref "R27") (pin "2") (pinfunction "2_2") (pintype "passive"))
      (node (ref "R5") (pin "1") (pinfunction "1_1") (pintype "passive"))
      (node (ref "R6") (pin "2") (pinfunction "2_2") (pintype "passive"))
      (node (ref "R8") (pin "1") (pinfunction "1_1") (pintype "passive"))
      (node (ref "U1") (pin "1") (pinfunction "VBAT_1") (pintype "power_in"))
      (node (ref "U1") (pin "24") (pinfunction "VDD_1_24") (pintype "power_in"))
      (node (ref "U1") (pin "36") (pinfunction "VDD_2_36") (pintype "power_in"))
      (node (ref "U1") (pin "48") (pinfunction "VDD_3_48") (pintype "power_in"))
      (node (ref "U4") (pin "5") (pinfunction "VOUT_5") (pintype "passive"))
    )
    (net (code "27") (name "GND") (class "Default")
      (node (ref "C1") (pin "1") (pinfunction "1_1") (pintype "passive"))
      (node (ref "C11") (pin "1") (pinfunction "1_1") (pintype "passive"))
      (node (ref "C12") (pin "1") (pinfunction "1_1") (pintype "passive"))
      (node (ref "C25") (pin "1") (pinfunction "1_1") (pintype "passive"))
      (node (ref "C26") (pin "1") (pinfunction "1_1") (pintype "passive"))
      (node (ref "C27") (pin "1") (pinfunction "1_1") (pintype "passive"))
      (node (ref "C28") (pin "1") (pinfunction "1_1") (pintype "passive"))
      (node (ref "C29") (pin "1") (pinfunction "1_1") (pintype "passive"))
      (node (ref "C37") (pin "1") (pinfunction "1_1") (pintype "passive"))
      (node (ref "C4") (pin "1") (pinfunction "1_1") (pintype "passive"))
      (node (ref "C40") (pin "2") (pinfunction "2_2") (pintype "passive"))
      (node (ref "C41") (pin "2") (pinfunction "2_2") (pintype "passive"))
      (node (ref "C43") (pin "1") (pinfunction "1_1") (pintype "passive"))
      (node (ref "C45") (pin "1") (pinfunction "1_1") (pintype "passive"))
      (node (ref "C49") (pin "2") (pinfunction "2_2") (pintype "passive"))
      (node (ref "C50") (pin "2") (pinfunction "2_2") (pintype "passive"))
      (node (ref "C51") (pin "2") (pinfunction "2_2") (pintype "passive"))
      (node (ref "C52") (pin "2") (pinfunction "2_2") (pintype "passive"))
      (node (ref "C53") (pin "1") (pinfunction "1_1") (pintype "passive"))
      (node (ref "C58") (pin "1") (pinfunction "1_1") (pintype "passive"))
      (node (ref "FB3") (pin "1") (pinfunction "1_1") (pintype "passive"))
      (node (ref "FB5") (pin "1") (pinfunction "1_1") (pintype "passive"))
      (node (ref "FB7") (pin "1") (pinfunction "1_1") (pintype "passive"))
      (node (ref "IC1") (pin "1") (pinfunction "A0_1") (pintype "input"))
      (node (ref "IC1") (pin "2") (pinfunction "A1_2") (pintype "input"))
      (node (ref "IC1") (pin "3") (pinfunction "A2_3") (pintype "input"))
      (node (ref "IC1") (pin "4") (pinfunction "GND_4") (pintype "passive"))
      (node (ref "JP3") (pin "1") (pinfunction "1_1") (pintype "passive"))
      (node (ref "JP4") (pin "1") (pinfunction "1_1") (pintype "passive"))
      (node (ref "LED4") (pin "2") (pinfunction "K_2") (pintype "passive"))
      (node (ref "P1") (pin "1") (pinfunction "1_1") (pintype "passive"))
      (node (ref "P2") (pin "2") (pinfunction "2_2") (pintype "passive"))
      (node (ref "P3") (pin "2") (pinfunction "2_2") (pintype "passive"))
      (node (ref "Q1") (pin "2") (pinfunction "S_2") (pintype "passive"))
      (node (ref "R18") (pin "2") (pinfunction "2_2") (pintype "passive"))
      (node (ref "R19") (pin "2") (pinfunction "2_2") (pintype "passive"))
      (node (ref "R20") (pin "1") (pinfunction "1_1") (pintype "passive"))
      (node (ref "R3") (pin "2") (pinfunction "2_2") (pintype "passive"))
      (node (ref "R7") (pin "1") (pinfunction "1_1") (pintype "passive"))
      (node (ref "R9") (pin "2") (pinfunction "2_2") (pintype "passive"))
      (node (ref "SW1") (pin "2") (pinfunction "2_2") (pintype "passive"))
      (node (ref "SW2") (pin "2") (pinfunction "2_2") (pintype "passive"))
      (node (ref "SW3") (pin "1") (pinfunction "1_1") (pintype "passive"))
      (node (ref "U1") (pin "23") (pinfunction "VSS_1_23") (pintype "power_in"))
      (node (ref "U1") (pin "35") (pinfunction "VSS_2_35") (pintype "power_in"))
      (node (ref "U1") (pin "47") (pinfunction "VSS_3_47") (pintype "power_in"))
      (node (ref "U3") (pin "3") (pinfunction "VSSA_3") (pintype "passive"))
      (node (ref "U4") (pin "2") (pinfunction "GND_2") (pintype "passive"))
      (node (ref "USBC1") (pin "0") (pinfunction "0_0") (pintype "passive"))
      (node (ref "USBC1") (pin "A1") (pinfunction "GND_A1") (pintype "passive"))
      (node (ref "USBC1") (pin "A12") (pinfunction "GND_A12") (pintype "passive"))
      (node (ref "USBC1") (pin "B1") (pinfunction "GND_B1") (pintype "passive"))
      (node (ref "USBC1") (pin "B12") (pinfunction "GND_B12") (pintype "passive"))
    )
    (net (code "28") (name "GNDA") (class "Default")
      (node (ref "C38") (pin "1") (pinfunction "1_1") (pintype "passive"))
      (node (ref "C39") (pin "1") (pinfunction "1_1") (pintype "passive"))
      (node (ref "C44") (pin "1") (pinfunction "1_1") (pintype "passive"))
      (node (ref "C46") (pin "1") (pinfunction "1_1") (pintype "passive"))
      (node (ref "C47") (pin "1") (pinfunction "1_1") (pintype "passive"))
      (node (ref "C48") (pin "1") (pinfunction "1_1") (pintype "passive"))
      (node (ref "C54") (pin "1") (pinfunction "1_1") (pintype "passive"))
      (node (ref "C55") (pin "1") (pinfunction "1_1") (pintype "passive"))
      (node (ref "FB7") (pin "2") (pinfunction "2_2") (pintype "passive"))
      (node (ref "U3") (pin "27") (pinfunction "GND_HP_27") (pintype "passive"))
      (node (ref "U3") (pin "36") (pinfunction "AVSS_36") (pintype "passive"))
      (node (ref "U3") (pin "44") (pinfunction "GNDCP_44") (pintype "passive"))
    )
    (net (code "29") (name "GNDRF") (class "Default")
      (node (ref "BK1") (pin "33") (pinfunction "33_33") (pintype "passive"))
      (node (ref "C17") (pin "2") (pinfunction "2_2") (pintype "passive"))
      (node (ref "C18") (pin "2") (pinfunction "2_2") (pintype "passive"))
      (node (ref "C19") (pin "2") (pinfunction "2_2") (pintype "passive"))
      (node (ref "C2") (pin "1") (pinfunction "1_1") (pintype "passive"))
      (node (ref "C20") (pin "2") (pinfunction "2_2") (pintype "passive"))
      (node (ref "C21") (pin "2") (pinfunction "2_2") (pintype "passive"))
      (node (ref "C23") (pin "1") (pinfunction "1_1") (pintype "passive"))
      (node (ref "C24") (pin "2") (pinfunction "2_2") (pintype "passive"))
      (node (ref "C3") (pin "1") (pinfunction "1_1") (pintype "passive"))
      (node (ref "C32") (pin "1") (pinfunction "1_1") (pintype "passive"))
      (node (ref "C33") (pin "1") (pinfunction "1_1") (pintype "passive"))
      (node (ref "C34") (pin "1") (pinfunction "1_1") (pintype "passive"))
      (node (ref "C35") (pin "2") (pinfunction "2_2") (pintype "passive"))
      (node (ref "C36") (pin "2") (pinfunction "2_2") (pintype "passive"))
      (node (ref "C5") (pin "1") (pinfunction "1_1") (pintype "passive"))
      (node (ref "C56") (pin "2") (pinfunction "2_2") (pintype "passive"))
      (node (ref "C57") (pin "1") (pinfunction "1_1") (pintype "passive"))
      (node (ref "C6") (pin "1") (pinfunction "1_1") (pintype "passive"))
      (node (ref "C7") (pin "1") (pinfunction "1_1") (pintype "passive"))
      (node (ref "C8") (pin "1") (pinfunction "1_1") (pintype "passive"))
      (node (ref "FB5") (pin "2") (pinfunction "2_2") (pintype "passive"))
      (node (ref "JP1") (pin "2") (pinfunction "GND_2") (pintype "passive"))
      (node (ref "JP1") (pin "3") (pinfunction "GND_3") (pintype "passive"))
      (node (ref "JP2") (pin "2") (pinfunction "GND_2") (pintype "passive"))
      (node (ref "JP2") (pin "3") (pinfunction "GND_3") (pintype "passive"))
      (node (ref "L5") (pin "1") (pinfunction "1_1") (pintype "passive"))
      (node (ref "R14") (pin "1") (pinfunction "1_1") (pintype "passive"))
      (node (ref "U2") (pin "2") (pinfunction "GND_2") (pintype "passive"))
    )
    (net (code "30") (name "Net-(BK1-EXCN)") (class "Default")
      (node (ref "BK1") (pin "12") (pinfunction "EXCN_12") (pintype "passive"))
      (node (ref "C22") (pin "2") (pinfunction "2_2") (pintype "passive"))
    )
    (net (code "31") (name "Net-(BK1-EXCP)") (class "Default")
      (node (ref "BK1") (pin "11") (pinfunction "EXCP_11") (pintype "passive"))
      (node (ref "C22") (pin "1") (pinfunction "1_1") (pintype "passive"))
    )
    (net (code "32") (name "Net-(BK1-TXON)") (class "Default")
      (node (ref "BK1") (pin "9") (pinfunction "TXON_9") (pintype "passive"))
      (node (ref "C10") (pin "1") (pinfunction "1_1") (pintype "passive"))
      (node (ref "L1") (pin "1") (pinfunction "1_1") (pintype "passive"))
    )
    (net (code "33") (name "Net-(BK1-TXOP)") (class "Default")
      (node (ref "BK1") (pin "10") (pinfunction "TXOP_10") (pintype "passive"))
      (node (ref "C16") (pin "1") (pinfunction "1_1") (pintype "passive"))
      (node (ref "L2") (pin "1") (pinfunction "1_1") (pintype "passive"))
    )
    (net (code "34") (name "Net-(BK1-VCCTX)") (class "Default")
      (node (ref "BK1") (pin "7") (pinfunction "VCCTX_7") (pintype "passive"))
      (node (ref "FB1") (pin "2") (pinfunction "2_2") (pintype "passive"))
    )
    (net (code "35") (name "Net-(BK1-VDDDIG)") (class "Default")
      (node (ref "BK1") (pin "17") (pinfunction "VDDDIG_17") (pintype "passive"))
      (node (ref "C33") (pin "2") (pinfunction "2_2") (pintype "passive"))
    )
    (net (code "36") (name "Net-(BK1-VDDVCO)") (class "Default")
      (node (ref "BK1") (pin "1") (pinfunction "VDDVCO_1") (pintype "passive"))
      (node (ref "C7") (pin "2") (pinfunction "2_2") (pintype "passive"))
    )
    (net (code "37") (name "Net-(BK1-XI)") (class "Default")
      (node (ref "BK1") (pin "31") (pinfunction "XI_31") (pintype "passive"))
      (node (ref "C20") (pin "1") (pinfunction "1_1") (pintype "passive"))
      (node (ref "Y1") (pin "1") (pinfunction "OSC1_1") (pintype "passive"))
    )
    (net (code "38") (name "Net-(BK1-XO)") (class "Default")
      (node (ref "BK1") (pin "30") (pinfunction "XO_30") (pintype "passive"))
      (node (ref "C21") (pin "1") (pinfunction "1_1") (pintype "passive"))
      (node (ref "Y1") (pin "2") (pinfunction "OSC2_2") (pintype "passive"))
    )
    (net (code "39") (name "Net-(C2-Pad2)") (class "Default")
      (node (ref "C2") (pin "2") (pinfunction "2_2") (pintype "passive"))
      (node (ref "C3") (pin "2") (pinfunction "2_2") (pintype "passive"))
      (node (ref "FB1") (pin "1") (pinfunction "1_1") (pintype "passive"))
      (node (ref "L1") (pin "2") (pinfunction "2_2") (pintype "passive"))
      (node (ref "L2") (pin "2") (pinfunction "2_2") (pintype "passive"))
    )
    (net (code "40") (name "Net-(C10-Pad2)") (class "Default")
      (node (ref "C10") (pin "2") (pinfunction "2_2") (pintype "passive"))
      (node (ref "C8") (pin "2") (pinfunction "2_2") (pintype "passive"))
      (node (ref "L4") (pin "2") (pinfunction "2_2") (pintype "passive"))
    )
    (net (code "41") (name "Net-(C15-Pad1)") (class "Default")
      (node (ref "C15") (pin "1") (pinfunction "1_1") (pintype "passive"))
      (node (ref "C16") (pin "2") (pinfunction "2_2") (pintype "passive"))
      (node (ref "L5") (pin "2") (pinfunction "2_2") (pintype "passive"))
    )
    (net (code "42") (name "Net-(C15-Pad2)") (class "Default")
      (node (ref "C15") (pin "2") (pinfunction "2_2") (pintype "passive"))
      (node (ref "C9") (pin "1") (pinfunction "1_1") (pintype "passive"))
      (node (ref "L4") (pin "1") (pinfunction "1_1") (pintype "passive"))
    )
    (net (code "43") (name "Net-(D1-K)") (class "Default")
      (node (ref "D1") (pin "2") (pinfunction "K_2") (pintype "passive"))
      (node (ref "Q2") (pin "3") (pinfunction "C_3") (pintype "passive"))
      (node (ref "R11") (pin "2") (pinfunction "2_2") (pintype "passive"))
    )
    (net (code "44") (name "Net-(IC1-SCL)") (class "Default")
      (node (ref "IC1") (pin "6") (pinfunction "SCL_6") (pintype "input"))
      (node (ref "R26") (pin "1") (pinfunction "1_1") (pintype "passive"))
      (node (ref "U3") (pin "18") (pinfunction "I2C_SCL_18") (pintype "passive"))
    )
    (net (code "45") (name "Net-(IC1-SDA)") (class "Default")
      (node (ref "IC1") (pin "5") (pinfunction "SDA_5") (pintype "bidirectional"))
      (node (ref "R27") (pin "1") (pinfunction "1_1") (pintype "passive"))
      (node (ref "U3") (pin "19") (pinfunction "I2C_SDA_19") (pintype "passive"))
    )
    (net (code "46") (name "Net-(JP1-ANT)") (class "Default")
      (node (ref "C18") (pin "1") (pinfunction "1_1") (pintype "passive"))
      (node (ref "C9") (pin "2") (pinfunction "2_2") (pintype "passive"))
      (node (ref "JP1") (pin "1") (pinfunction "ANT_1") (pintype "passive"))
      (node (ref "L3") (pin "2") (pinfunction "2_2") (pintype "passive"))
    )
    (net (code "47") (name "Net-(JP2-ANT)") (class "Default")
      (node (ref "C17") (pin "1") (pinfunction "1_1") (pintype "passive"))
      (node (ref "JP2") (pin "1") (pinfunction "ANT_1") (pintype "passive"))
      (node (ref "L3") (pin "1") (pinfunction "1_1") (pintype "passive"))
    )
    (net (code "48") (name "Net-(LED1-A)") (class "Default")
      (node (ref "LED1") (pin "1") (pinfunction "A_1") (pintype "passive"))
      (node (ref "R1") (pin "1") (pinfunction "1_1") (pintype "passive"))
    )
    (net (code "49") (name "Net-(LED1-K)") (class "Default")
      (node (ref "LED1") (pin "2") (pinfunction "K_2") (pintype "passive"))
      (node (ref "Q1") (pin "3") (pinfunction "D_3") (pintype "passive"))
    )
    (net (code "50") (name "Net-(LED2-A)") (class "Default")
      (node (ref "LED2") (pin "1") (pinfunction "A_1") (pintype "passive"))
      (node (ref "R2") (pin "1") (pinfunction "1_1") (pintype "passive"))
    )
    (net (code "51") (name "Net-(LED3-A)") (class "Default")
      (node (ref "LED3") (pin "1") (pinfunction "A_1") (pintype "passive"))
      (node (ref "R6") (pin "1") (pinfunction "1_1") (pintype "passive"))
    )
    (net (code "52") (name "Net-(LED4-A)") (class "Default")
      (node (ref "LED4") (pin "1") (pinfunction "A_1") (pintype "passive"))
      (node (ref "R25") (pin "1") (pinfunction "1_1") (pintype "passive"))
    )
    (net (code "53") (name "Net-(Q1-G)") (class "Default")
      (node (ref "Q1") (pin "1") (pinfunction "G_1") (pintype "passive"))
      (node (ref "R4") (pin "1") (pinfunction "1_1") (pintype "passive"))
      (node (ref "R7") (pin "2") (pinfunction "2_2") (pintype "passive"))
    )
    (net (code "54") (name "Net-(Q2-B)") (class "Default")
      (node (ref "Q2") (pin "1") (pinfunction "B_1") (pintype "passive"))
      (node (ref "R12") (pin "2") (pinfunction "2_2") (pintype "passive"))
    )
    (net (code "55") (name "Net-(Q3-B)") (class "Default")
      (node (ref "Q3") (pin "1") (pinfunction "B_1") (pintype "passive"))
      (node (ref "R13") (pin "2") (pinfunction "2_2") (pintype "passive"))
    )
    (net (code "56") (name "Net-(Q3-C)") (class "Default")
      (node (ref "Q3") (pin "3") (pinfunction "C_3") (pintype "passive"))
      (node (ref "R15") (pin "1") (pinfunction "1_1") (pintype "passive"))
    )
    (net (code "57") (name "Net-(U1A-PA3)") (class "Default")
      (node (ref "R4") (pin "2") (pinfunction "2_2") (pintype "passive"))
      (node (ref "U1") (pin "13") (pinfunction "PA3_13") (pintype "bidirectional"))
    )
    (net (code "58") (name "Net-(U1A-PB0)") (class "Default")
      (node (ref "C1") (pin "2") (pinfunction "2_2") (pintype "passive"))
      (node (ref "SW1") (pin "1") (pinfunction "1_1") (pintype "passive"))
      (node (ref "U1") (pin "18") (pinfunction "PB0_18") (pintype "bidirectional"))
    )
    (net (code "59") (name "Net-(U1A-PB1)") (class "Default")
      (node (ref "C4") (pin "2") (pinfunction "2_2") (pintype "passive"))
      (node (ref "SW2") (pin "1") (pinfunction "1_1") (pintype "passive"))
      (node (ref "U1") (pin "19") (pinfunction "PB1_19") (pintype "bidirectional"))
    )
    (net (code "60") (name "Net-(U1A-PB2)") (class "Default")
      (node (ref "R3") (pin "1") (pinfunction "1_1") (pintype "passive"))
      (node (ref "U1") (pin "20") (pinfunction "PB2_20") (pintype "bidirectional"))
    )
    (net (code "61") (name "Net-(U1A-PD0-OSC_IN)") (class "Default")
      (node (ref "C25") (pin "2") (pinfunction "2_2") (pintype "passive"))
      (node (ref "U1") (pin "5") (pinfunction "PD0-OSC_IN_5") (pintype "bidirectional"))
      (node (ref "Y2") (pin "2") (pinfunction "OSC2_2") (pintype "passive"))
    )
    (net (code "62") (name "Net-(U1A-PD1)") (class "Default")
      (node (ref "C29") (pin "2") (pinfunction "2_2") (pintype "passive"))
      (node (ref "U1") (pin "6") (pinfunction "PD1_6") (pintype "bidirectional"))
      (node (ref "Y2") (pin "1") (pinfunction "OSC1_1") (pintype "passive"))
    )
    (net (code "63") (name "Net-(U3-CFLYN)") (class "Default")
      (node (ref "C42") (pin "1") (pinfunction "1_1") (pintype "passive"))
      (node (ref "U3") (pin "43") (pinfunction "CFLYN_43") (pintype "passive"))
    )
    (net (code "64") (name "Net-(U3-CFLYP)") (class "Default")
      (node (ref "C42") (pin "2") (pinfunction "2_2") (pintype "passive"))
      (node (ref "U3") (pin "45") (pinfunction "CFLYP_45") (pintype "passive"))
    )
    (net (code "65") (name "Net-(U3-HPVDD)") (class "Default")
      (node (ref "C46") (pin "2") (pinfunction "2_2") (pintype "passive"))
      (node (ref "U3") (pin "40") (pinfunction "HPVDD_40") (pintype "passive"))
      (node (ref "U3") (pin "41") (pinfunction "VCPP_41") (pintype "passive"))
    )
    (net (code "66") (name "Net-(U3-HPVSS)") (class "Default")
      (node (ref "C44") (pin "2") (pinfunction "2_2") (pintype "passive"))
      (node (ref "U3") (pin "37") (pinfunction "HPVSS_37") (pintype "passive"))
      (node (ref "U3") (pin "42") (pinfunction "VCPN_42") (pintype "passive"))
    )
    (net (code "67") (name "Net-(U3-INSEL)") (class "Default")
      (node (ref "R24") (pin "1") (pinfunction "1_1") (pintype "passive"))
      (node (ref "U3") (pin "9") (pinfunction "INSEL_9") (pintype "passive"))
    )
    (net (code "68") (name "Net-(U3-LEDO)") (class "Default")
      (node (ref "R25") (pin "2") (pinfunction "2_2") (pintype "passive"))
      (node (ref "U3") (pin "8") (pinfunction "LEDO_8") (pintype "passive"))
    )
    (net (code "69") (name "Net-(U3-TEST)") (class "Default")
      (node (ref "R19") (pin "1") (pinfunction "1_1") (pintype "passive"))
      (node (ref "U3") (pin "47") (pinfunction "TEST_47") (pintype "passive"))
    )
    (net (code "70") (name "Net-(U3-V12)") (class "Default")
      (node (ref "C45") (pin "2") (pinfunction "2_2") (pintype "passive"))
      (node (ref "U3") (pin "4") (pinfunction "V12_4") (pintype "passive"))
    )
    (net (code "71") (name "Net-(U3-VMID)") (class "Default")
      (node (ref "C47") (pin "2") (pinfunction "2_2") (pintype "passive"))
      (node (ref "C48") (pin "2") (pinfunction "2_2") (pintype "passive"))
      (node (ref "U3") (pin "35") (pinfunction "VMID_35") (pintype "passive"))
    )
    (net (code "72") (name "Net-(U4-EN)") (class "Default")
      (node (ref "R21") (pin "1") (pinfunction "1_1") (pintype "passive"))
      (node (ref "U4") (pin "3") (pinfunction "EN_3") (pintype "passive"))
    )
    (net (code "73") (name "Net-(USBC1-CC1)") (class "Default")
      (node (ref "R20") (pin "2") (pinfunction "2_2") (pintype "passive"))
      (node (ref "USBC1") (pin "A5") (pinfunction "CC1_A5") (pintype "passive"))
    )
    (net (code "74") (name "Net-(USBC1-CC2)") (class "Default")
      (node (ref "R18") (pin "1") (pinfunction "1_1") (pintype "passive"))
      (node (ref "USBC1") (pin "B5") (pinfunction "CC2_B5") (pintype "passive"))
    )
    (net (code "75") (name "RF3V3") (class "Default")
      (node (ref "BK1") (pin "13") (pinfunction "VCCAUD_13") (pintype "passive"))
      (node (ref "BK1") (pin "16") (pinfunction "VCCDIG_16") (pintype "passive"))
      (node (ref "BK1") (pin "2") (pinfunction "VCCVCO_2") (pintype "passive"))
      (node (ref "BK1") (pin "24") (pinfunction "VCCIF_24") (pintype "passive"))
      (node (ref "BK1") (pin "28") (pinfunction "VCCDVCO_28") (pintype "passive"))
      (node (ref "BK1") (pin "29") (pinfunction "VCCXTAL_29") (pintype "passive"))
      (node (ref "BK1") (pin "32") (pinfunction "VCCPLL_32") (pintype "passive"))
      (node (ref "BK1") (pin "4") (pinfunction "VCCB_4") (pintype "passive"))
      (node (ref "BK1") (pin "8") (pinfunction "VCCPA_8") (pintype "passive"))
      (node (ref "C19") (pin "1") (pinfunction "1_1") (pintype "passive"))
      (node (ref "C23") (pin "2") (pinfunction "2_2") (pintype "passive"))
      (node (ref "C24") (pin "1") (pinfunction "1_1") (pintype "passive"))
      (node (ref "C32") (pin "2") (pinfunction "2_2") (pintype "passive"))
      (node (ref "C34") (pin "2") (pinfunction "2_2") (pintype "passive"))
      (node (ref "C36") (pin "1") (pinfunction "1_1") (pintype "passive"))
      (node (ref "C5") (pin "2") (pinfunction "2_2") (pintype "passive"))
      (node (ref "C56") (pin "1") (pinfunction "1_1") (pintype "passive"))
      (node (ref "C57") (pin "2") (pinfunction "2_2") (pintype "passive"))
      (node (ref "C6") (pin "2") (pinfunction "2_2") (pintype "passive"))
      (node (ref "U2") (pin "5") (pinfunction "VOUT_5") (pintype "passive"))
    )
    (net (code "76") (name "USB_5V") (class "Default")
      (node (ref "C26") (pin "2") (pinfunction "2_2") (pintype "passive"))
      (node (ref "C35") (pin "1") (pinfunction "1_1") (pintype "passive"))
      (node (ref "C50") (pin "1") (pinfunction "1_1") (pintype "passive"))
      (node (ref "C51") (pin "1") (pinfunction "1_1") (pintype "passive"))
      (node (ref "FB4") (pin "1") (pinfunction "1_1") (pintype "passive"))
      (node (ref "R21") (pin "2") (pinfunction "2_2") (pintype "passive"))
      (node (ref "U2") (pin "1") (pinfunction "VIN_1") (pintype "passive"))
      (node (ref "U4") (pin "1") (pinfunction "VIN_1") (pintype "passive"))
    )
    (net (code "77") (name "VBUS") (class "Default")
      (node (ref "C27") (pin "2") (pinfunction "2_2") (pintype "passive"))
      (node (ref "C28") (pin "2") (pinfunction "2_2") (pintype "passive"))
      (node (ref "FB4") (pin "2") (pinfunction "2_2") (pintype "passive"))
      (node (ref "U3") (pin "1") (pinfunction "VBUS_1") (pintype "passive"))
      (node (ref "USBC1") (pin "A4") (pinfunction "VBUS_A4") (pintype "passive"))
      (node (ref "USBC1") (pin "A9") (pinfunction "VBUS_A9") (pintype "passive"))
      (node (ref "USBC1") (pin "B4") (pinfunction "VBUS_B4") (pintype "passive"))
      (node (ref "USBC1") (pin "B9") (pinfunction "VBUS_B9") (pintype "passive"))
    )
    (net (code "78") (name "VDDA") (class "Default")
      (node (ref "C13") (pin "2") (pinfunction "2_2") (pintype "passive"))
      (node (ref "C14") (pin "2") (pinfunction "2_2") (pintype "passive"))
      (node (ref "FB2") (pin "2") (pinfunction "2_2") (pintype "passive"))
      (node (ref "U1") (pin "9") (pinfunction "VDDA_9") (pintype "power_in"))
    )
    (net (code "79") (name "VSSA") (class "Default")
      (node (ref "C13") (pin "1") (pinfunction "1_1") (pintype "passive"))
      (node (ref "C14") (pin "1") (pinfunction "1_1") (pintype "passive"))
      (node (ref "FB3") (pin "2") (pinfunction "2_2") (pintype "passive"))
      (node (ref "U1") (pin "8") (pinfunction "VSSA_8") (pintype "power_in"))
    )
    (net (code "80") (name "unconnected-(BK1-GPIO2-Pad20)") (class "Default")
      (node (ref "BK1") (pin "20") (pinfunction "GPIO2_20") (pintype "passive"))
    )
    (net (code "81") (name "unconnected-(BK1-GPIO4-Pad25)") (class "Default")
      (node (ref "BK1") (pin "25") (pinfunction "GPIO4_25") (pintype "passive+no_connect"))
    )
    (net (code "82") (name "unconnected-(BK1-IRQ-Pad27)") (class "Default")
      (node (ref "BK1") (pin "27") (pinfunction "IRQ_27") (pintype "passive+no_connect"))
    )
    (net (code "83") (name "unconnected-(BK1-MICN-Pad14)") (class "Default")
      (node (ref "BK1") (pin "14") (pinfunction "MICN_14") (pintype "passive+no_connect"))
    )
    (net (code "84") (name "unconnected-(BK1-MICP-Pad15)") (class "Default")
      (node (ref "BK1") (pin "15") (pinfunction "MICP_15") (pintype "passive+no_connect"))
    )
    (net (code "85") (name "unconnected-(BK1-NC-Pad5)") (class "Default")
      (node (ref "BK1") (pin "5") (pinfunction "NC_5") (pintype "passive"))
    )
    (net (code "86") (name "unconnected-(BK1-NC-Pad6)") (class "Default")
      (node (ref "BK1") (pin "6") (pinfunction "NC_6") (pintype "passive"))
    )
    (net (code "87") (name "unconnected-(IC1-WP-Pad7)") (class "Default")
      (node (ref "IC1") (pin "7") (pinfunction "WP_7") (pintype "passive+no_connect"))
    )
    (net (code "88") (name "unconnected-(U1A-PA2-Pad12)") (class "Default")
      (node (ref "U1") (pin "12") (pinfunction "PA2_12") (pintype "bidirectional"))
    )
    (net (code "89") (name "unconnected-(U1A-PA4-Pad14)") (class "Default")
      (node (ref "U1") (pin "14") (pinfunction "PA4_14") (pintype "bidirectional"))
    )
    (net (code "90") (name "unconnected-(U1A-PA7-Pad17)") (class "Default")
      (node (ref "U1") (pin "17") (pinfunction "PA7_17") (pintype "bidirectional"))
    )
    (net (code "91") (name "unconnected-(U1A-PA8-Pad29)") (class "Default")
      (node (ref "U1") (pin "29") (pinfunction "PA8_29") (pintype "bidirectional"))
    )
    (net (code "92") (name "unconnected-(U1A-PA11-Pad32)") (class "Default")
      (node (ref "U1") (pin "32") (pinfunction "PA11_32") (pintype "bidirectional"))
    )
    (net (code "93") (name "unconnected-(U1A-PA15-Pad38)") (class "Default")
      (node (ref "U1") (pin "38") (pinfunction "PA15_38") (pintype "bidirectional"))
    )
    (net (code "94") (name "unconnected-(U1A-PB3-Pad39)") (class "Default")
      (node (ref "U1") (pin "39") (pinfunction "PB3_39") (pintype "bidirectional"))
    )
    (net (code "95") (name "unconnected-(U1A-PB4-Pad40)") (class "Default")
      (node (ref "U1") (pin "40") (pinfunction "PB4_40") (pintype "bidirectional"))
    )
    (net (code "96") (name "unconnected-(U1A-PB5-Pad41)") (class "Default")
      (node (ref "U1") (pin "41") (pinfunction "PB5_41") (pintype "bidirectional"))
    )
    (net (code "97") (name "unconnected-(U1A-PB8-Pad45)") (class "Default")
      (node (ref "U1") (pin "45") (pinfunction "PB8_45") (pintype "bidirectional"))
    )
    (net (code "98") (name "unconnected-(U1A-PB9-Pad46)") (class "Default")
      (node (ref "U1") (pin "46") (pinfunction "PB9_46") (pintype "bidirectional"))
    )
    (net (code "99") (name "unconnected-(U1A-PB10-Pad21)") (class "Default")
      (node (ref "U1") (pin "21") (pinfunction "PB10_21") (pintype "bidirectional"))
    )
    (net (code "100") (name "unconnected-(U1A-PB11-Pad22)") (class "Default")
      (node (ref "U1") (pin "22") (pinfunction "PB11_22") (pintype "bidirectional"))
    )
    (net (code "101") (name "unconnected-(U1A-PB12-Pad25)") (class "Default")
      (node (ref "U1") (pin "25") (pinfunction "PB12_25") (pintype "bidirectional"))
    )
    (net (code "102") (name "unconnected-(U1A-PB13-Pad26)") (class "Default")
      (node (ref "U1") (pin "26") (pinfunction "PB13_26") (pintype "bidirectional"))
    )
    (net (code "103") (name "unconnected-(U1A-PB14-Pad27)") (class "Default")
      (node (ref "U1") (pin "27") (pinfunction "PB14_27") (pintype "bidirectional"))
    )
    (net (code "104") (name "unconnected-(U1A-PB15-Pad28)") (class "Default")
      (node (ref "U1") (pin "28") (pinfunction "PB15_28") (pintype "bidirectional"))
    )
    (net (code "105") (name "unconnected-(U1A-PC13-TAMPER-RTC-Pad2)") (class "Default")
      (node (ref "U1") (pin "2") (pinfunction "PC13-TAMPER-RTC_2") (pintype "bidirectional"))
    )
    (net (code "106") (name "unconnected-(U1A-PC14-OSC32_IN-Pad3)") (class "Default")
      (node (ref "U1") (pin "3") (pinfunction "PC14-OSC32_IN_3") (pintype "bidirectional"))
    )
    (net (code "107") (name "unconnected-(U1A-PC15-OSC32_OUT-Pad4)") (class "Default")
      (node (ref "U1") (pin "4") (pinfunction "PC15-OSC32_OUT_4") (pintype "bidirectional"))
    )
    (net (code "108") (name "unconnected-(U2-NC-Pad4)") (class "Default")
      (node (ref "U2") (pin "4") (pinfunction "NC_4") (pintype "passive+no_connect"))
    )
    (net (code "109") (name "unconnected-(U3-EQ3D_LED-Pad48)") (class "Default")
      (node (ref "U3") (pin "48") (pinfunction "EQ3D_LED_48") (pintype "passive+no_connect"))
    )
    (net (code "110") (name "unconnected-(U3-KEY_RENC_INV-Pad7)") (class "Default")
      (node (ref "U3") (pin "7") (pinfunction "KEY_RENC_INV_7") (pintype "passive+no_connect"))
    )
    (net (code "111") (name "unconnected-(U3-LHPOUT-Pad39)") (class "Default")
      (node (ref "U3") (pin "39") (pinfunction "LHPOUT_39") (pintype "passive+no_connect"))
    )
    (net (code "112") (name "unconnected-(U3-MIC1-Pad29)") (class "Default")
      (node (ref "U3") (pin "29") (pinfunction "MIC1_29") (pintype "passive+no_connect"))
    )
    (net (code "113") (name "unconnected-(U3-MIC1N-Pad31)") (class "Default")
      (node (ref "U3") (pin "31") (pinfunction "MIC1N_31") (pintype "passive+no_connect"))
    )
    (net (code "114") (name "unconnected-(U3-MIC1P-Pad32)") (class "Default")
      (node (ref "U3") (pin "32") (pinfunction "MIC1P_32") (pintype "passive+no_connect"))
    )
    (net (code "115") (name "unconnected-(U3-MIC2P-Pad33)") (class "Default")
      (node (ref "U3") (pin "33") (pinfunction "MIC2P_33") (pintype "passive+no_connect"))
    )
    (net (code "116") (name "unconnected-(U3-MICBIAS-Pad30)") (class "Default")
      (node (ref "U3") (pin "30") (pinfunction "MICBIAS_30") (pintype "passive+no_connect"))
    )
    (net (code "117") (name "unconnected-(U3-MSEL-Pad10)") (class "Default")
      (node (ref "U3") (pin "10") (pinfunction "MSEL_10") (pintype "passive+no_connect"))
    )
    (net (code "118") (name "unconnected-(U3-NEXT_TRACK-Pad20)") (class "Default")
      (node (ref "U3") (pin "20") (pinfunction "NEXT_TRACK_20") (pintype "passive+no_connect"))
    )
    (net (code "119") (name "unconnected-(U3-PALY_PAUSE-Pad22)") (class "Default")
      (node (ref "U3") (pin "22") (pinfunction "PALY_PAUSE_22") (pintype "passive+no_connect"))
    )
    (net (code "120") (name "unconnected-(U3-PLAY_EN-Pad16)") (class "Default")
      (node (ref "U3") (pin "16") (pinfunction "PLAY_EN_16") (pintype "passive+no_connect"))
    )
    (net (code "121") (name "unconnected-(U3-PRE_TACK-Pad21)") (class "Default")
      (node (ref "U3") (pin "21") (pinfunction "PRE_TACK_21") (pintype "passive+no_connect"))
    )
    (net (code "122") (name "unconnected-(U3-REC_EN-Pad17)") (class "Default")
      (node (ref "U3") (pin "17") (pinfunction "REC_EN_17") (pintype "passive+no_connect"))
    )
    (net (code "123") (name "unconnected-(U3-RHPOUT-Pad38)") (class "Default")
      (node (ref "U3") (pin "38") (pinfunction "RHPOUT_38") (pintype "passive+no_connect"))
    )
    (net (code "124") (name "unconnected-(U3-RING2-Pad28)") (class "Default")
      (node (ref "U3") (pin "28") (pinfunction "RING2_28") (pintype "passive+no_connect"))
    )
    (net (code "125") (name "unconnected-(U3-SLEEVE-Pad26)") (class "Default")
      (node (ref "U3") (pin "26") (pinfunction "SLEEVE_26") (pintype "passive+no_connect"))
    )
    (net (code "126") (name "unconnected-(U3-STEREO_MIC-Pad13)") (class "Default")
      (node (ref "U3") (pin "13") (pinfunction "STEREO_MIC_13") (pintype "passive+no_connect"))
    )
    (net (code "127") (name "unconnected-(U3-STOP-Pad24)") (class "Default")
      (node (ref "U3") (pin "24") (pinfunction "STOP_24") (pintype "passive+no_connect"))
    )
    (net (code "128") (name "unconnected-(U3-VOLDN-Pad15)") (class "Default")
      (node (ref "U3") (pin "15") (pinfunction "VOLDN_15") (pintype "passive+no_connect"))
    )
    (net (code "129") (name "unconnected-(U3-VP_MUTE-Pad25)") (class "Default")
      (node (ref "U3") (pin "25") (pinfunction "VP_MUTE_25") (pintype "passive+no_connect"))
    )
    (net (code "130") (name "unconnected-(U3-VR_MUTE-Pad23)") (class "Default")
      (node (ref "U3") (pin "23") (pinfunction "VR_MUTE_23") (pintype "passive+no_connect"))
    )
    (net (code "131") (name "unconnected-(U4-NC-Pad4)") (class "Default")
      (node (ref "U4") (pin "4") (pinfunction "NC_4") (pintype "passive+no_connect"))
    )
    (net (code "132") (name "unconnected-(USBC1-SBU1-PadA8)") (class "Default")
      (node (ref "USBC1") (pin "A8") (pinfunction "SBU1_A8") (pintype "passive"))
    )
    (net (code "133") (name "unconnected-(USBC1-SBU2-PadB8)") (class "Default")
      (node (ref "USBC1") (pin "B8") (pinfunction "SBU2_B8") (pintype "passive"))
    )
  )
)
